# SCH_onboard_2025-02-03.net
KiCad netlist of a schematic drawn in EasyEDA
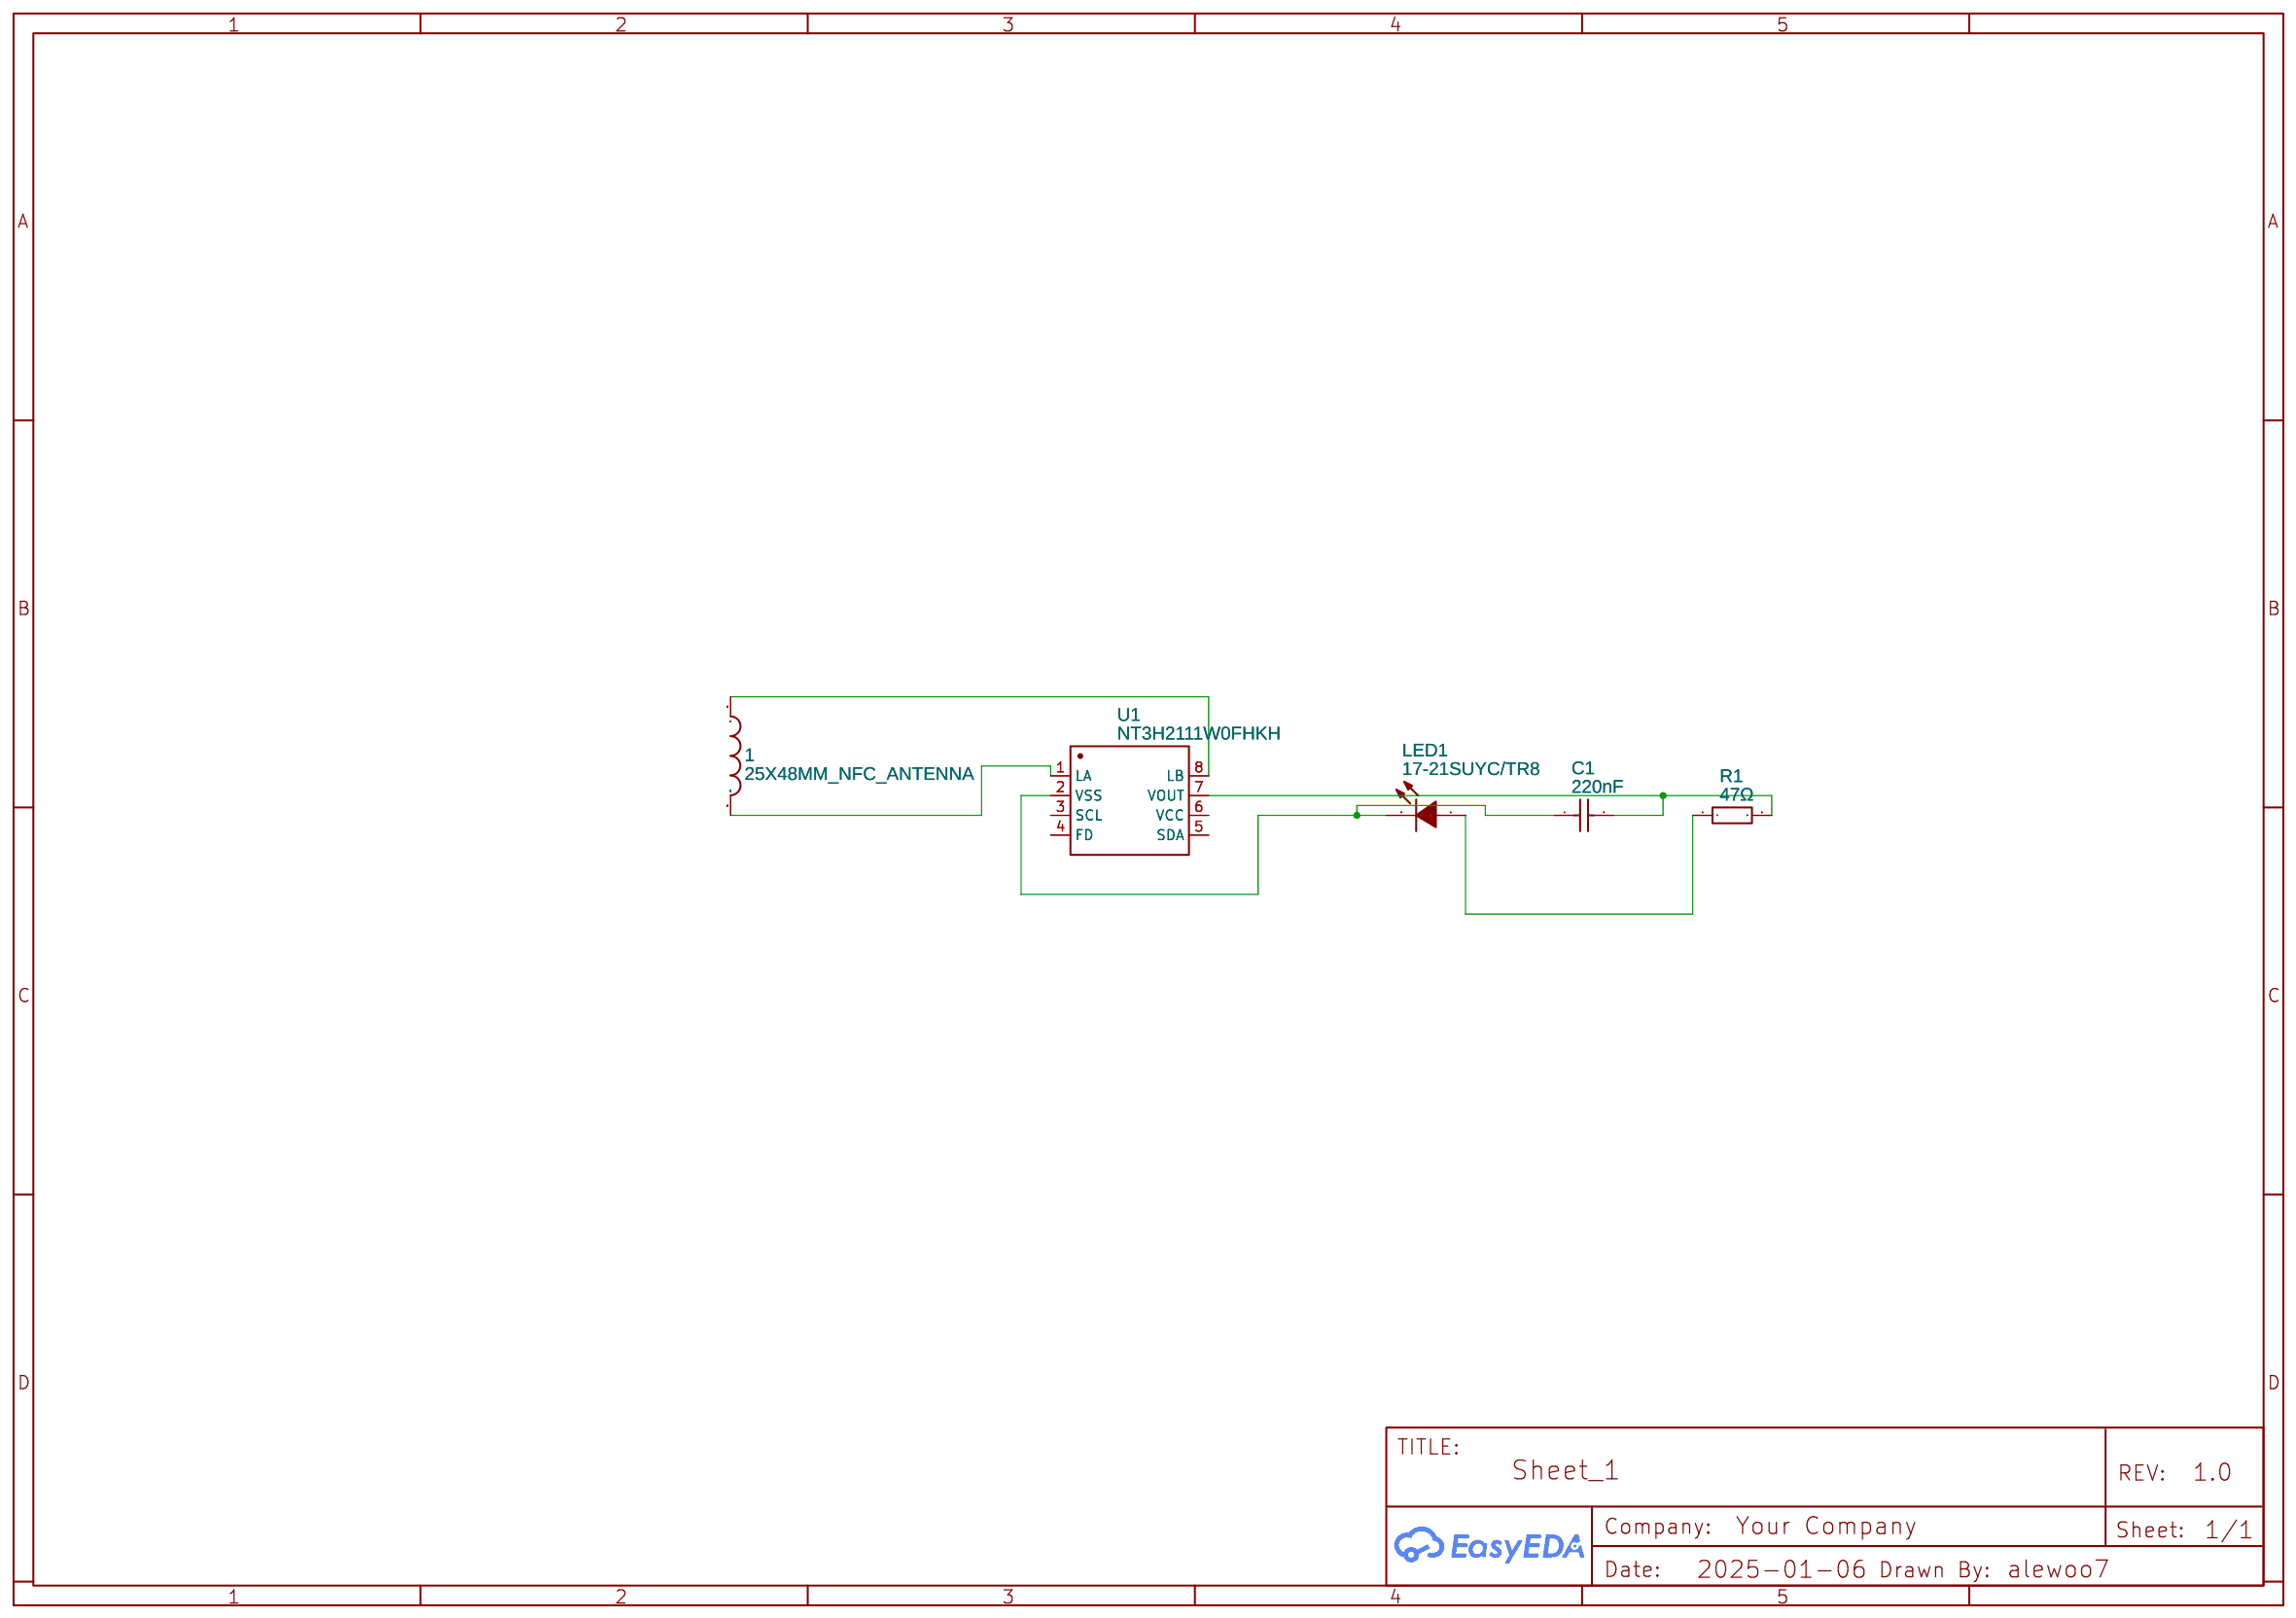
[diagram p0: schematic sheet]

(export (version "E")
  (design (tool "Eeschema 10.0.6"))
  (components
    (comp (ref "1") (value "25X48MM_NFC_ANTENNA") (libsource (lib "") (part "25X48MM_NFC_ANTENNA")))
    (comp (ref "C1")
      (value "220nF")
      (fields
        (field (name "Manufacturer Part") "CL10B224KA8NNNC")
        (field (name "Manufacturer") "SAMSUNG(三星)")
      )
      (libsource (lib "") (part "CL10B224KA8NNNC"))
    )
    (comp (ref "LED1")
      (value "17-21SUYC/TR8")
      (fields (field (name "Manufacturer Part") "KT-0805黄灯") (field (name "Manufacturer") "KENTO"))
      (libsource (lib "") (part "17-21SUYC/TR8"))
    )
    (comp (ref "R1")
      (value "47Ω")
      (fields
        (field (name "Manufacturer Part") "0603WAF470JT5E")
        (field (name "Manufacturer") "UNI-ROYAL(厚声)")
      )
      (libsource (lib "") (part "0603WAF470JT5E"))
    )
    (comp (ref "U1")
      (value "NT3H2111W0FHKH")
      (fields (field (name "Manufacturer") "NXP(恩智浦)"))
      (libsource (lib "") (part "NT3H2111W0FHKH"))
    )
  )
  (nets
    (net (code "1") (name "Net-(LED1-+)") (class "Default")
      (node (ref "LED1") (pin "1") (pinfunction "+_1") (pintype "unspecified"))
      (node (ref "R1") (pin "1") (pinfunction "1_1") (pintype "input"))
    )
    (net (code "2") (name "Net-(LED1--)") (class "Default")
      (node (ref "C1") (pin "1") (pinfunction "1_1") (pintype "input"))
      (node (ref "LED1") (pin "2") (pinfunction "-_2") (pintype "unspecified"))
      (node (ref "U1") (pin "2") (pinfunction "VSS_2") (pintype "unspecified"))
    )
    (net (code "3") (name "Net-(U1-LA)") (class "Default")
      (node (ref "1") (pin "P$2") (pinfunction "P$2_P$2") (pintype "bidirectional"))
      (node (ref "U1") (pin "1") (pinfunction "LA_1") (pintype "unspecified"))
    )
    (net (code "4") (name "Net-(U1-LB)") (class "Default")
      (node (ref "1") (pin "P$1") (pinfunction "P$1_P$1") (pintype "bidirectional"))
      (node (ref "U1") (pin "8") (pinfunction "LB_8") (pintype "unspecified"))
    )
    (net (code "5") (name "Net-(U1-VOUT)") (class "Default")
      (node (ref "C1") (pin "2") (pinfunction "2_2") (pintype "input"))
      (node (ref "R1") (pin "2") (pinfunction "2_2") (pintype "input"))
      (node (ref "U1") (pin "7") (pinfunction "VOUT_7") (pintype "unspecified"))
    )
    (net (code "6") (name "unconnected-(U1-FD-Pad4)") (class "Default")
      (node (ref "U1") (pin "4") (pinfunction "FD_4") (pintype "unspecified"))
    )
    (net (code "7") (name "unconnected-(U1-SCL-Pad3)") (class "Default")
      (node (ref "U1") (pin "3") (pinfunction "SCL_3") (pintype "unspecified"))
    )
    (net (code "8") (name "unconnected-(U1-SDA-Pad5)") (class "Default")
      (node (ref "U1") (pin "5") (pinfunction "SDA_5") (pintype "unspecified"))
    )
    (net (code "9") (name "unconnected-(U1-VCC-Pad6)") (class "Default")
      (node (ref "U1") (pin "6") (pinfunction "VCC_6") (pintype "unspecified"))
    )
  )
)
